# bmp280_spi.net
KiCad netlist of a schematic drawn in Altium Designer
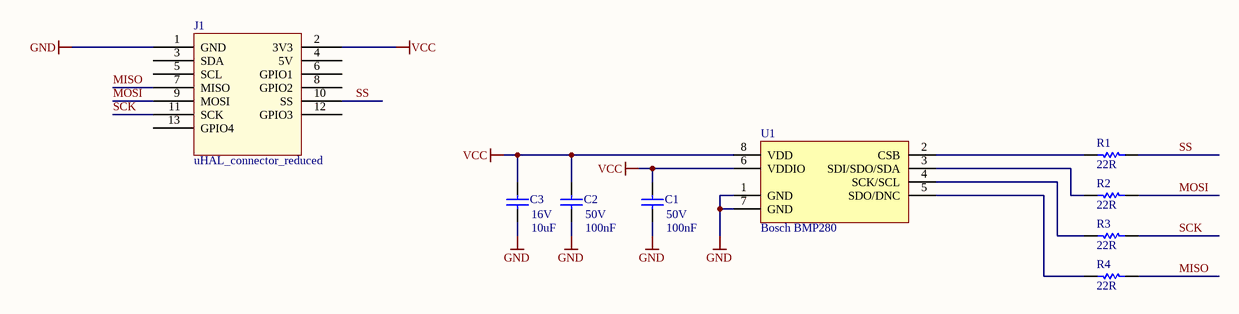
[diagram p0: bmp280_spi.SchDoc]

(export (version "E")
  (design (tool "Eeschema 10.0.6"))
  (components
    (comp (ref "C1")
      (value "Murata GCM188R71H104KA57D")
      (footprint "CAPC1608X90X35ML10T15")
      (description "CAP CER 0.1UF 50V 10% X7R 0603")
      (fields (field (name "CAPACITANCE") "100nF") (field (name "VOLTAGE RATING (DC)") "50V"))
      (libsource (lib "CommunityVault") (part "CMP-119667-3"))
    )
    (comp (ref "C2")
      (value "Murata GCM188R71H104KA57D")
      (footprint "CAPC1608X90X35ML10T15")
      (description "CAP CER 0.1UF 50V 10% X7R 0603")
      (fields (field (name "CAPACITANCE") "100nF") (field (name "VOLTAGE RATING (DC)") "50V"))
      (libsource (lib "CommunityVault") (part "CMP-119667-3"))
    )
    (comp (ref "C3")
      (value "~")
      (footprint "CAPC1608X90X35ML10T15")
      (fields (field (name "CAPACITANCE") "10uF") (field (name "VOLTAGE RATING (DC)") "16V"))
      (libsource (lib "CommunityVault") (part "CMP-119667-3"))
    )
    (comp (ref "J1")
      (value "uHAL_connector_reduced")
      (footprint "PCB-45ncoppm4oopozvqifsq-1")
      (description "connector for uHAL with reduced pin number")
      (libsource (lib "CommunityVault") (part "CMP-2q23h2cwhjlfm8s6r7i8-1"))
    )
    (comp (ref "R1")
      (value "22R")
      (footprint "RESC1608X05N")
      (libsource (lib "CommunityVault") (part "CMP-31acf99032f6ee6b-1"))
    )
    (comp (ref "R2")
      (value "22R")
      (footprint "RESC1608X05N")
      (libsource (lib "CommunityVault") (part "CMP-31acf99032f6ee6b-1"))
    )
    (comp (ref "R3")
      (value "22R")
      (footprint "RESC1608X05N")
      (libsource (lib "CommunityVault") (part "CMP-31acf99032f6ee6b-1"))
    )
    (comp (ref "R4")
      (value "22R")
      (footprint "RESC1608X05N")
      (libsource (lib "CommunityVault") (part "CMP-31acf99032f6ee6b-1"))
    )
    (comp (ref "U1")
      (value "Bosch BMP280")
      (footprint "PCB-7ktgzhb423iat7xn8psi-1")
      (description "P-Sensor SPI I2C SMD")
      (fields (field (name "MANUFACTURER PART NUMBER") "BMP280"))
      (libsource (lib "CommunityVault") (part "SYM-f1e0397949ec2e27-1"))
    )
  )
  (nets
    (net (code "1") (name "/MISO") (class "Default")
      (node (ref "J1") (pin "7") (pinfunction "MISO_7") (pintype "passive"))
      (node (ref "R4") (pin "1") (pinfunction "1_1") (pintype "passive"))
    )
    (net (code "2") (name "/MOSI") (class "Default")
      (node (ref "J1") (pin "9") (pinfunction "MOSI_9") (pintype "passive"))
      (node (ref "R2") (pin "1") (pinfunction "1_1") (pintype "passive"))
    )
    (net (code "3") (name "/SCK") (class "Default")
      (node (ref "J1") (pin "11") (pinfunction "SCK_11") (pintype "passive"))
      (node (ref "R3") (pin "1") (pinfunction "1_1") (pintype "passive"))
    )
    (net (code "4") (name "/SS") (class "Default")
      (node (ref "J1") (pin "10") (pinfunction "SS_10") (pintype "passive"))
      (node (ref "R1") (pin "1") (pinfunction "1_1") (pintype "passive"))
    )
    (net (code "5") (name "GND") (class "Default")
      (node (ref "C1") (pin "2") (pinfunction "2_2") (pintype "passive"))
      (node (ref "C2") (pin "2") (pinfunction "2_2") (pintype "passive"))
      (node (ref "C3") (pin "2") (pinfunction "2_2") (pintype "passive"))
      (node (ref "J1") (pin "1") (pinfunction "GND_1") (pintype "passive"))
      (node (ref "U1") (pin "1") (pinfunction "GND_1") (pintype "power_in"))
      (node (ref "U1") (pin "7") (pinfunction "GND_7") (pintype "power_in"))
    )
    (net (code "6") (name "Net-(U1-CSB)") (class "Default")
      (node (ref "R1") (pin "2") (pinfunction "2_2") (pintype "passive"))
      (node (ref "U1") (pin "2") (pinfunction "CSB_2") (pintype "passive"))
    )
    (net (code "7") (name "Net-(U1-SCK{slash}SCL)") (class "Default")
      (node (ref "R3") (pin "2") (pinfunction "2_2") (pintype "passive"))
      (node (ref "U1") (pin "4") (pinfunction "SCK/SCL_4") (pintype "passive"))
    )
    (net (code "8") (name "Net-(U1-SDI{slash}SDO{slash}SDA)") (class "Default")
      (node (ref "R2") (pin "2") (pinfunction "2_2") (pintype "passive"))
      (node (ref "U1") (pin "3") (pinfunction "SDI/SDO/SDA_3") (pintype "passive"))
    )
    (net (code "9") (name "Net-(U1-SDO{slash}DNC)") (class "Default")
      (node (ref "R4") (pin "2") (pinfunction "2_2") (pintype "passive"))
      (node (ref "U1") (pin "5") (pinfunction "SDO/DNC_5") (pintype "passive"))
    )
    (net (code "10") (name "VCC") (class "Default")
      (node (ref "C1") (pin "1") (pinfunction "1_1") (pintype "passive"))
      (node (ref "C2") (pin "1") (pinfunction "1_1") (pintype "passive"))
      (node (ref "C3") (pin "1") (pinfunction "1_1") (pintype "passive"))
      (node (ref "J1") (pin "2") (pinfunction "3V3_2") (pintype "passive"))
      (node (ref "U1") (pin "6") (pinfunction "VDDIO_6") (pintype "power_in"))
      (node (ref "U1") (pin "8") (pinfunction "VDD_8") (pintype "power_in"))
    )
    (net (code "11") (name "unconnected-(J1-5V-Pad4)") (class "Default")
      (node (ref "J1") (pin "4") (pinfunction "5V_4") (pintype "passive"))
    )
    (net (code "12") (name "unconnected-(J1-GPIO1-Pad6)") (class "Default")
      (node (ref "J1") (pin "6") (pinfunction "GPIO1_6") (pintype "passive"))
    )
    (net (code "13") (name "unconnected-(J1-GPIO2-Pad8)") (class "Default")
      (node (ref "J1") (pin "8") (pinfunction "GPIO2_8") (pintype "passive"))
    )
    (net (code "14") (name "unconnected-(J1-GPIO3-Pad12)") (class "Default")
      (node (ref "J1") (pin "12") (pinfunction "GPIO3_12") (pintype "passive"))
    )
    (net (code "15") (name "unconnected-(J1-GPIO4-Pad13)") (class "Default")
      (node (ref "J1") (pin "13") (pinfunction "GPIO4_13") (pintype "passive"))
    )
    (net (code "16") (name "unconnected-(J1-SCL-Pad5)") (class "Default")
      (node (ref "J1") (pin "5") (pinfunction "SCL_5") (pintype "passive"))
    )
    (net (code "17") (name "unconnected-(J1-SDA-Pad3)") (class "Default")
      (node (ref "J1") (pin "3") (pinfunction "SDA_3") (pintype "passive"))
    )
  )
)
